# GSM_USB_Port.net
KiCad netlist of a schematic drawn in Altium Designer
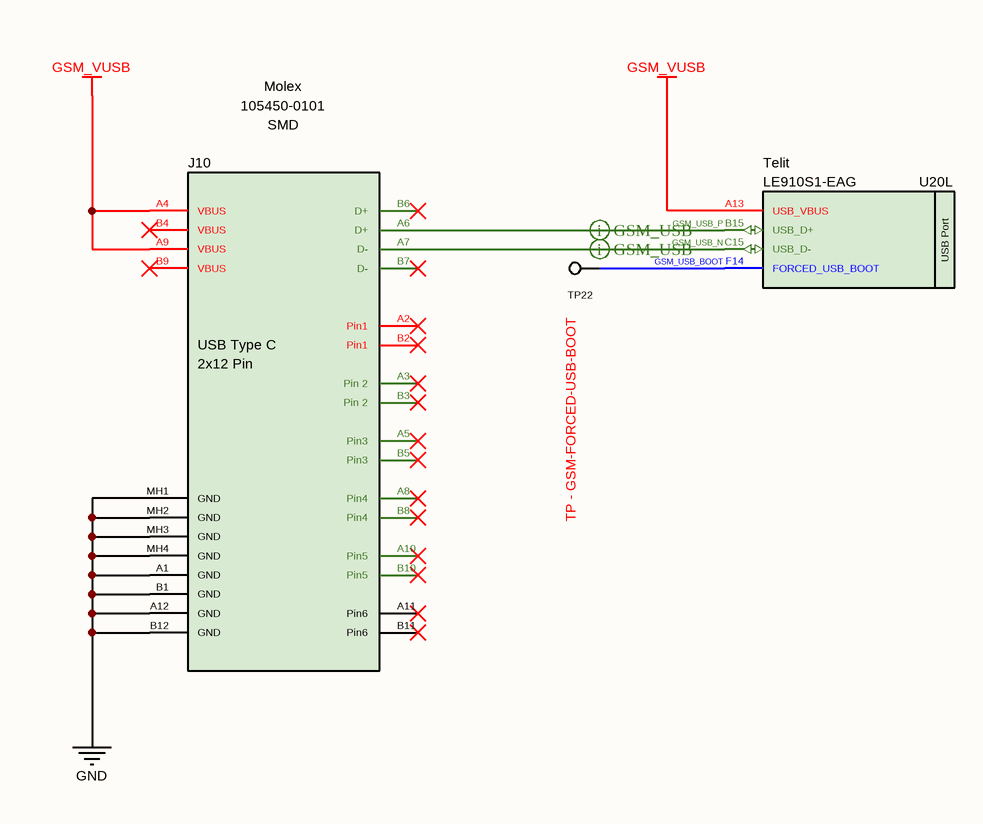
[diagram p0: GSM USB Port.SchDoc]

(export (version "E")
  (design (tool "Eeschema 10.0.6"))
  (components
    (comp (ref "J10")
      (value "105450-0101")
      (footprint "USB Type C - Molex 105450-0101")
      (description "USB Shielded I/O Receptacle; Type C; Right Angle; Surface Mount; Gold over Nickel")
      (fields
        (field (name "MANUFACTURER NAME") "Molex")
        (field (name "MANUFACTURER PART NUMBER") "105450-0101")
        (field (name "CASE") "SMD")
      )
      (libsource (lib "Akkoyun") (part "Connector - USB Type C SMD Connector"))
    )
    (comp (ref "TP22")
      (value "TP - GSM-FORCED-USB-BOOT")
      (footprint "TP")
      (description "Test Point")
      (libsource (lib "Akkoyun") (part "PCB - Test Point"))
    )
    (comp (ref "U20")
      (value "LE910S1-EAG LTE GSM Module")
      (footprint "LE910 GSM Modem")
      (description "Telit LE910S1-EAG GPRS/GNSS Module")
      (fields
        (field (name "MANUFACTURER PART NUMBER") "LE910S1-EAG")
        (field (name "MANUFACTURER NAME") "Telit")
      )
      (libsource (lib "Akkoyun") (part "IC - LE910S1-EAG"))
    )
  )
  (nets
    (net (code "1") (name "/GSM_USB_BOOT") (class "Default")
      (node (ref "TP22") (pin "1") (pinfunction "1_1") (pintype "passive"))
      (node (ref "U20") (pin "F14") (pinfunction "FORCED_USB_BOOT_F14") (pintype "passive"))
    )
    (net (code "2") (name "/GSM_USB_N") (class "Default")
      (node (ref "J10") (pin "A7") (pinfunction "D-_A7") (pintype "passive"))
      (node (ref "U20") (pin "C15") (pinfunction "USB_D-_C15") (pintype "bidirectional"))
    )
    (net (code "3") (name "/GSM_USB_P") (class "Default")
      (node (ref "J10") (pin "A6") (pinfunction "D+_A6") (pintype "passive"))
      (node (ref "U20") (pin "B15") (pinfunction "USB_D+_B15") (pintype "bidirectional"))
    )
    (net (code "4") (name "GND") (class "Default")
      (node (ref "J10") (pin "A1") (pinfunction "GND_A1") (pintype "passive"))
      (node (ref "J10") (pin "A12") (pinfunction "GND_A12") (pintype "passive"))
      (node (ref "J10") (pin "B1") (pinfunction "GND_B1") (pintype "passive"))
      (node (ref "J10") (pin "B12") (pinfunction "GND_B12") (pintype "passive"))
      (node (ref "J10") (pin "MH1") (pinfunction "GND_MH1") (pintype "passive"))
      (node (ref "J10") (pin "MH2") (pinfunction "GND_MH2") (pintype "passive"))
      (node (ref "J10") (pin "MH3") (pinfunction "GND_MH3") (pintype "passive"))
      (node (ref "J10") (pin "MH4") (pinfunction "GND_MH4") (pintype "passive"))
    )
    (net (code "5") (name "GSM_VUSB") (class "Default")
      (node (ref "J10") (pin "A4") (pinfunction "VBUS_A4") (pintype "passive"))
      (node (ref "J10") (pin "A9") (pinfunction "VBUS_A9") (pintype "passive"))
      (node (ref "U20") (pin "A13") (pinfunction "USB_VBUS_A13") (pintype "power_in"))
    )
    (net (code "6") (name "unconnected-(J10-D+-PadB6)") (class "Default")
      (node (ref "J10") (pin "B6") (pinfunction "D+_B6") (pintype "passive+no_connect"))
    )
    (net (code "7") (name "unconnected-(J10-D--PadB7)") (class "Default")
      (node (ref "J10") (pin "B7") (pinfunction "D-_B7") (pintype "passive+no_connect"))
    )
    (net (code "8") (name "unconnected-(J10-Pin1-PadA2)") (class "Default")
      (node (ref "J10") (pin "A2") (pinfunction "Pin1_A2") (pintype "passive+no_connect"))
    )
    (net (code "9") (name "unconnected-(J10-Pin1-PadB2)") (class "Default")
      (node (ref "J10") (pin "B2") (pinfunction "Pin1_B2") (pintype "passive+no_connect"))
    )
    (net (code "10") (name "unconnected-(J10-Pin3-PadA5)") (class "Default")
      (node (ref "J10") (pin "A5") (pinfunction "Pin3_A5") (pintype "passive+no_connect"))
    )
    (net (code "11") (name "unconnected-(J10-Pin3-PadB5)") (class "Default")
      (node (ref "J10") (pin "B5") (pinfunction "Pin3_B5") (pintype "passive+no_connect"))
    )
    (net (code "12") (name "unconnected-(J10-Pin4-PadA8)") (class "Default")
      (node (ref "J10") (pin "A8") (pinfunction "Pin4_A8") (pintype "passive+no_connect"))
    )
    (net (code "13") (name "unconnected-(J10-Pin4-PadB8)") (class "Default")
      (node (ref "J10") (pin "B8") (pinfunction "Pin4_B8") (pintype "passive+no_connect"))
    )
    (net (code "14") (name "unconnected-(J10-Pin5-PadA10)") (class "Default")
      (node (ref "J10") (pin "A10") (pinfunction "Pin5_A10") (pintype "passive+no_connect"))
    )
    (net (code "15") (name "unconnected-(J10-Pin5-PadB10)") (class "Default")
      (node (ref "J10") (pin "B10") (pinfunction "Pin5_B10") (pintype "passive+no_connect"))
    )
    (net (code "16") (name "unconnected-(J10-Pin6-PadA11)") (class "Default")
      (node (ref "J10") (pin "A11") (pinfunction "Pin6_A11") (pintype "passive+no_connect"))
    )
    (net (code "17") (name "unconnected-(J10-Pin6-PadB11)") (class "Default")
      (node (ref "J10") (pin "B11") (pinfunction "Pin6_B11") (pintype "passive+no_connect"))
    )
    (net (code "18") (name "unconnected-(J10-Pin_2-PadA3)") (class "Default")
      (node (ref "J10") (pin "A3") (pinfunction "Pin_2_A3") (pintype "passive+no_connect"))
    )
    (net (code "19") (name "unconnected-(J10-Pin_2-PadB3)") (class "Default")
      (node (ref "J10") (pin "B3") (pinfunction "Pin_2_B3") (pintype "passive+no_connect"))
    )
    (net (code "20") (name "unconnected-(J10-VBUS-PadB4)") (class "Default")
      (node (ref "J10") (pin "B4") (pinfunction "VBUS_B4") (pintype "passive+no_connect"))
    )
    (net (code "21") (name "unconnected-(J10-VBUS-PadB9)") (class "Default")
      (node (ref "J10") (pin "B9") (pinfunction "VBUS_B9") (pintype "passive+no_connect"))
    )
  )
)
